# main.net
KiCad netlist of a schematic drawn in EAGLE
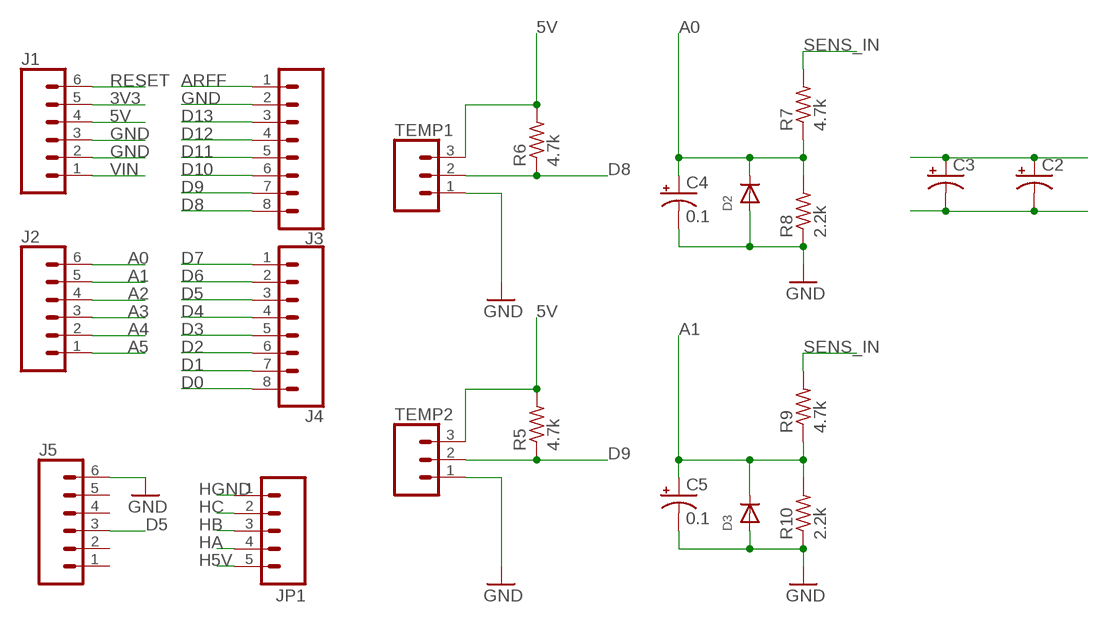
[diagram p0: schematic, sheet 1]

(export (version "E")
  (design (tool "Eeschema 10.0.6"))
  (components
    (comp (ref "C2")
      (value "C-POL-US_RADIAL-32MM-DIA")
      (footprint "eagle-import:CAPPRD1000W100D2275H3200B")
      (libsource (lib "eagle-import") (part "C-POL-USRADIAL-32MM-DIA_"))
    )
    (comp (ref "C3")
      (value "C-POL-US_RADIAL-32MM-DIA")
      (footprint "eagle-import:CAPPRD1000W100D2275H3200B")
      (libsource (lib "eagle-import") (part "C-POL-USRADIAL-32MM-DIA_"))
    )
    (comp (ref "C4")
      (value "0.1")
      (footprint "eagle-import:B45181A")
      (libsource (lib "eagle-import") (part "CPOL-USB45181A"))
    )
    (comp (ref "C5")
      (value "0.1")
      (footprint "eagle-import:B45181A")
      (libsource (lib "eagle-import") (part "CPOL-USB45181A"))
    )
    (comp (ref "D2")
      (value "DIODEDO-1N4148")
      (footprint "eagle-import:DO-1N4148")
      (libsource (lib "eagle-import") (part "DIODEDO-1N4148"))
    )
    (comp (ref "D3")
      (value "DIODEDO-1N4148")
      (footprint "eagle-import:DO-1N4148")
      (libsource (lib "eagle-import") (part "DIODEDO-1N4148"))
    )
    (comp (ref "J1")
      (value "CONN_06NO_SILK_FEMALE_PTH")
      (footprint "eagle-import:1X06_NO_SILK")
      (libsource (lib "eagle-import") (part "CONN_06NO_SILK_FEMALE_PTH"))
    )
    (comp (ref "J2")
      (value "CONN_06NO_SILK_FEMALE_PTH")
      (footprint "eagle-import:1X06_NO_SILK")
      (libsource (lib "eagle-import") (part "CONN_06NO_SILK_FEMALE_PTH"))
    )
    (comp (ref "J3")
      (value "CONN_08NO_SILK_FEMALE_PTH")
      (footprint "eagle-import:1X08_NO_SILK")
      (libsource (lib "eagle-import") (part "CONN_08NO_SILK_FEMALE_PTH"))
    )
    (comp (ref "J4")
      (value "CONN_08NO_SILK_FEMALE_PTH")
      (footprint "eagle-import:1X08_NO_SILK")
      (libsource (lib "eagle-import") (part "CONN_08NO_SILK_FEMALE_PTH"))
    )
    (comp (ref "J5")
      (value "CONN_06NO_SILK_FEMALE_PTH")
      (footprint "eagle-import:1X06_NO_SILK")
      (libsource (lib "eagle-import") (part "CONN_06NO_SILK_FEMALE_PTH"))
    )
    (comp (ref "JP1")
      (value "M05PTH")
      (footprint "eagle-import:1X05")
      (libsource (lib "eagle-import") (part "M05PTH"))
    )
    (comp (ref "R5")
      (value "4.7k")
      (footprint "eagle-import:0207_7")
      (libsource (lib "eagle-import") (part "R-US_0207/7"))
    )
    (comp (ref "R6")
      (value "4.7k")
      (footprint "eagle-import:0207_7")
      (libsource (lib "eagle-import") (part "R-US_0207/7"))
    )
    (comp (ref "R7")
      (value "4.7k")
      (footprint "eagle-import:0207_7")
      (libsource (lib "eagle-import") (part "R-US_0207/7"))
    )
    (comp (ref "R8")
      (value "2.2k")
      (footprint "eagle-import:0207_7")
      (libsource (lib "eagle-import") (part "R-US_0207/7"))
    )
    (comp (ref "R9")
      (value "4.7k")
      (footprint "eagle-import:0207_7")
      (libsource (lib "eagle-import") (part "R-US_0207/7"))
    )
    (comp (ref "R10")
      (value "2.2k")
      (footprint "eagle-import:0207_7")
      (libsource (lib "eagle-import") (part "R-US_0207/7"))
    )
    (comp (ref "TEMP1")
      (value "CONN_03")
      (footprint "eagle-import:1X03")
      (libsource (lib "eagle-import") (part "CONN_03"))
    )
    (comp (ref "TEMP2")
      (value "CONN_03")
      (footprint "eagle-import:1X03")
      (libsource (lib "eagle-import") (part "CONN_03"))
    )
  )
  (nets
    (net (code "1") (name "/3V3") (class "Default")
      (node (ref "J1") (pin "5") (pinfunction "5_5") (pintype "passive"))
    )
    (net (code "2") (name "/5V") (class "Default")
      (node (ref "J1") (pin "4") (pinfunction "4_4") (pintype "passive"))
      (node (ref "R5") (pin "2") (pinfunction "2_2") (pintype "passive"))
      (node (ref "R6") (pin "2") (pinfunction "2_2") (pintype "passive"))
      (node (ref "TEMP1") (pin "3") (pinfunction "3_3") (pintype "passive"))
      (node (ref "TEMP2") (pin "3") (pinfunction "3_3") (pintype "passive"))
    )
    (net (code "3") (name "/A0") (class "Default")
      (node (ref "C4") (pin "+") (pinfunction "+_+") (pintype "passive"))
      (node (ref "D2") (pin "C") (pinfunction "C_C") (pintype "passive"))
      (node (ref "J2") (pin "6") (pinfunction "6_6") (pintype "passive"))
      (node (ref "R7") (pin "1") (pinfunction "1_1") (pintype "passive"))
      (node (ref "R8") (pin "2") (pinfunction "2_2") (pintype "passive"))
    )
    (net (code "4") (name "/A1") (class "Default")
      (node (ref "C5") (pin "+") (pinfunction "+_+") (pintype "passive"))
      (node (ref "D3") (pin "C") (pinfunction "C_C") (pintype "passive"))
      (node (ref "J2") (pin "5") (pinfunction "5_5") (pintype "passive"))
      (node (ref "R10") (pin "2") (pinfunction "2_2") (pintype "passive"))
      (node (ref "R9") (pin "1") (pinfunction "1_1") (pintype "passive"))
    )
    (net (code "5") (name "/A2") (class "Default")
      (node (ref "J2") (pin "4") (pinfunction "4_4") (pintype "passive"))
    )
    (net (code "6") (name "/A3") (class "Default")
      (node (ref "J2") (pin "3") (pinfunction "3_3") (pintype "passive"))
    )
    (net (code "7") (name "/A4") (class "Default")
      (node (ref "J2") (pin "2") (pinfunction "2_2") (pintype "passive"))
    )
    (net (code "8") (name "/A5") (class "Default")
      (node (ref "J2") (pin "1") (pinfunction "1_1") (pintype "passive"))
    )
    (net (code "9") (name "/ARFF") (class "Default")
      (node (ref "J3") (pin "1") (pinfunction "1_1") (pintype "passive"))
    )
    (net (code "10") (name "/D0") (class "Default")
      (node (ref "J4") (pin "8") (pinfunction "8_8") (pintype "passive"))
    )
    (net (code "11") (name "/D1") (class "Default")
      (node (ref "J4") (pin "7") (pinfunction "7_7") (pintype "passive"))
    )
    (net (code "12") (name "/D2") (class "Default")
      (node (ref "J4") (pin "6") (pinfunction "6_6") (pintype "passive"))
    )
    (net (code "13") (name "/D3") (class "Default")
      (node (ref "J4") (pin "5") (pinfunction "5_5") (pintype "passive"))
    )
    (net (code "14") (name "/D4") (class "Default")
      (node (ref "J4") (pin "4") (pinfunction "4_4") (pintype "passive"))
    )
    (net (code "15") (name "/D5") (class "Default")
      (node (ref "J4") (pin "3") (pinfunction "3_3") (pintype "passive"))
      (node (ref "J5") (pin "3") (pinfunction "3_3") (pintype "passive"))
    )
    (net (code "16") (name "/D6") (class "Default")
      (node (ref "J4") (pin "2") (pinfunction "2_2") (pintype "passive"))
    )
    (net (code "17") (name "/D7") (class "Default")
      (node (ref "J4") (pin "1") (pinfunction "1_1") (pintype "passive"))
    )
    (net (code "18") (name "/D8") (class "Default")
      (node (ref "J3") (pin "8") (pinfunction "8_8") (pintype "passive"))
      (node (ref "R6") (pin "1") (pinfunction "1_1") (pintype "passive"))
      (node (ref "TEMP1") (pin "2") (pinfunction "2_2") (pintype "passive"))
    )
    (net (code "19") (name "/D9") (class "Default")
      (node (ref "J3") (pin "7") (pinfunction "7_7") (pintype "passive"))
      (node (ref "R5") (pin "1") (pinfunction "1_1") (pintype "passive"))
      (node (ref "TEMP2") (pin "2") (pinfunction "2_2") (pintype "passive"))
    )
    (net (code "20") (name "/D10") (class "Default")
      (node (ref "J3") (pin "6") (pinfunction "6_6") (pintype "passive"))
    )
    (net (code "21") (name "/D11") (class "Default")
      (node (ref "J3") (pin "5") (pinfunction "5_5") (pintype "passive"))
    )
    (net (code "22") (name "/D12") (class "Default")
      (node (ref "J3") (pin "4") (pinfunction "4_4") (pintype "passive"))
    )
    (net (code "23") (name "/D13") (class "Default")
      (node (ref "J3") (pin "3") (pinfunction "3_3") (pintype "passive"))
    )
    (net (code "24") (name "/H5V") (class "Default")
      (node (ref "JP1") (pin "5") (pinfunction "5_5") (pintype "passive"))
    )
    (net (code "25") (name "/HA") (class "Default")
      (node (ref "JP1") (pin "4") (pinfunction "4_4") (pintype "passive"))
    )
    (net (code "26") (name "/HB") (class "Default")
      (node (ref "JP1") (pin "3") (pinfunction "3_3") (pintype "passive"))
    )
    (net (code "27") (name "/HC") (class "Default")
      (node (ref "JP1") (pin "2") (pinfunction "2_2") (pintype "passive"))
    )
    (net (code "28") (name "/HGND") (class "Default")
      (node (ref "JP1") (pin "1") (pinfunction "1_1") (pintype "passive"))
    )
    (net (code "29") (name "/RESET") (class "Default")
      (node (ref "J1") (pin "6") (pinfunction "6_6") (pintype "passive"))
    )
    (net (code "30") (name "/SENS_IN") (class "Default")
      (node (ref "R7") (pin "2") (pinfunction "2_2") (pintype "passive"))
      (node (ref "R9") (pin "2") (pinfunction "2_2") (pintype "passive"))
    )
    (net (code "31") (name "/VIN") (class "Default")
      (node (ref "J1") (pin "1") (pinfunction "1_1") (pintype "passive"))
    )
    (net (code "32") (name "GND") (class "Default")
      (node (ref "C4") (pin "-") (pinfunction "-_-") (pintype "passive"))
      (node (ref "C5") (pin "-") (pinfunction "-_-") (pintype "passive"))
      (node (ref "D2") (pin "A") (pinfunction "A_A") (pintype "passive"))
      (node (ref "D3") (pin "A") (pinfunction "A_A") (pintype "passive"))
      (node (ref "J1") (pin "2") (pinfunction "2_2") (pintype "passive"))
      (node (ref "J1") (pin "3") (pinfunction "3_3") (pintype "passive"))
      (node (ref "J3") (pin "2") (pinfunction "2_2") (pintype "passive"))
      (node (ref "J5") (pin "6") (pinfunction "6_6") (pintype "passive"))
      (node (ref "R10") (pin "1") (pinfunction "1_1") (pintype "passive"))
      (node (ref "R8") (pin "1") (pinfunction "1_1") (pintype "passive"))
      (node (ref "TEMP1") (pin "1") (pinfunction "1_1") (pintype "passive"))
      (node (ref "TEMP2") (pin "1") (pinfunction "1_1") (pintype "passive"))
    )
    (net (code "33") (name "Net-(C2-+)") (class "Default")
      (node (ref "C2") (pin "1") (pinfunction "+_1") (pintype "passive"))
      (node (ref "C3") (pin "1") (pinfunction "+_1") (pintype "passive"))
    )
    (net (code "34") (name "Net-(C2--)") (class "Default")
      (node (ref "C2") (pin "2") (pinfunction "-_2") (pintype "passive"))
      (node (ref "C3") (pin "2") (pinfunction "-_2") (pintype "passive"))
    )
    (net (code "35") (name "unconnected-(J5-Pad1)") (class "Default")
      (node (ref "J5") (pin "1") (pinfunction "1_1") (pintype "passive"))
    )
    (net (code "36") (name "unconnected-(J5-Pad2)") (class "Default")
      (node (ref "J5") (pin "2") (pinfunction "2_2") (pintype "passive"))
    )
    (net (code "37") (name "unconnected-(J5-Pad4)") (class "Default")
      (node (ref "J5") (pin "4") (pinfunction "4_4") (pintype "passive"))
    )
    (net (code "38") (name "unconnected-(J5-Pad5)") (class "Default")
      (node (ref "J5") (pin "5") (pinfunction "5_5") (pintype "passive"))
    )
  )
)
